# USB_SAO.net
KiCad netlist of a schematic drawn in EAGLE
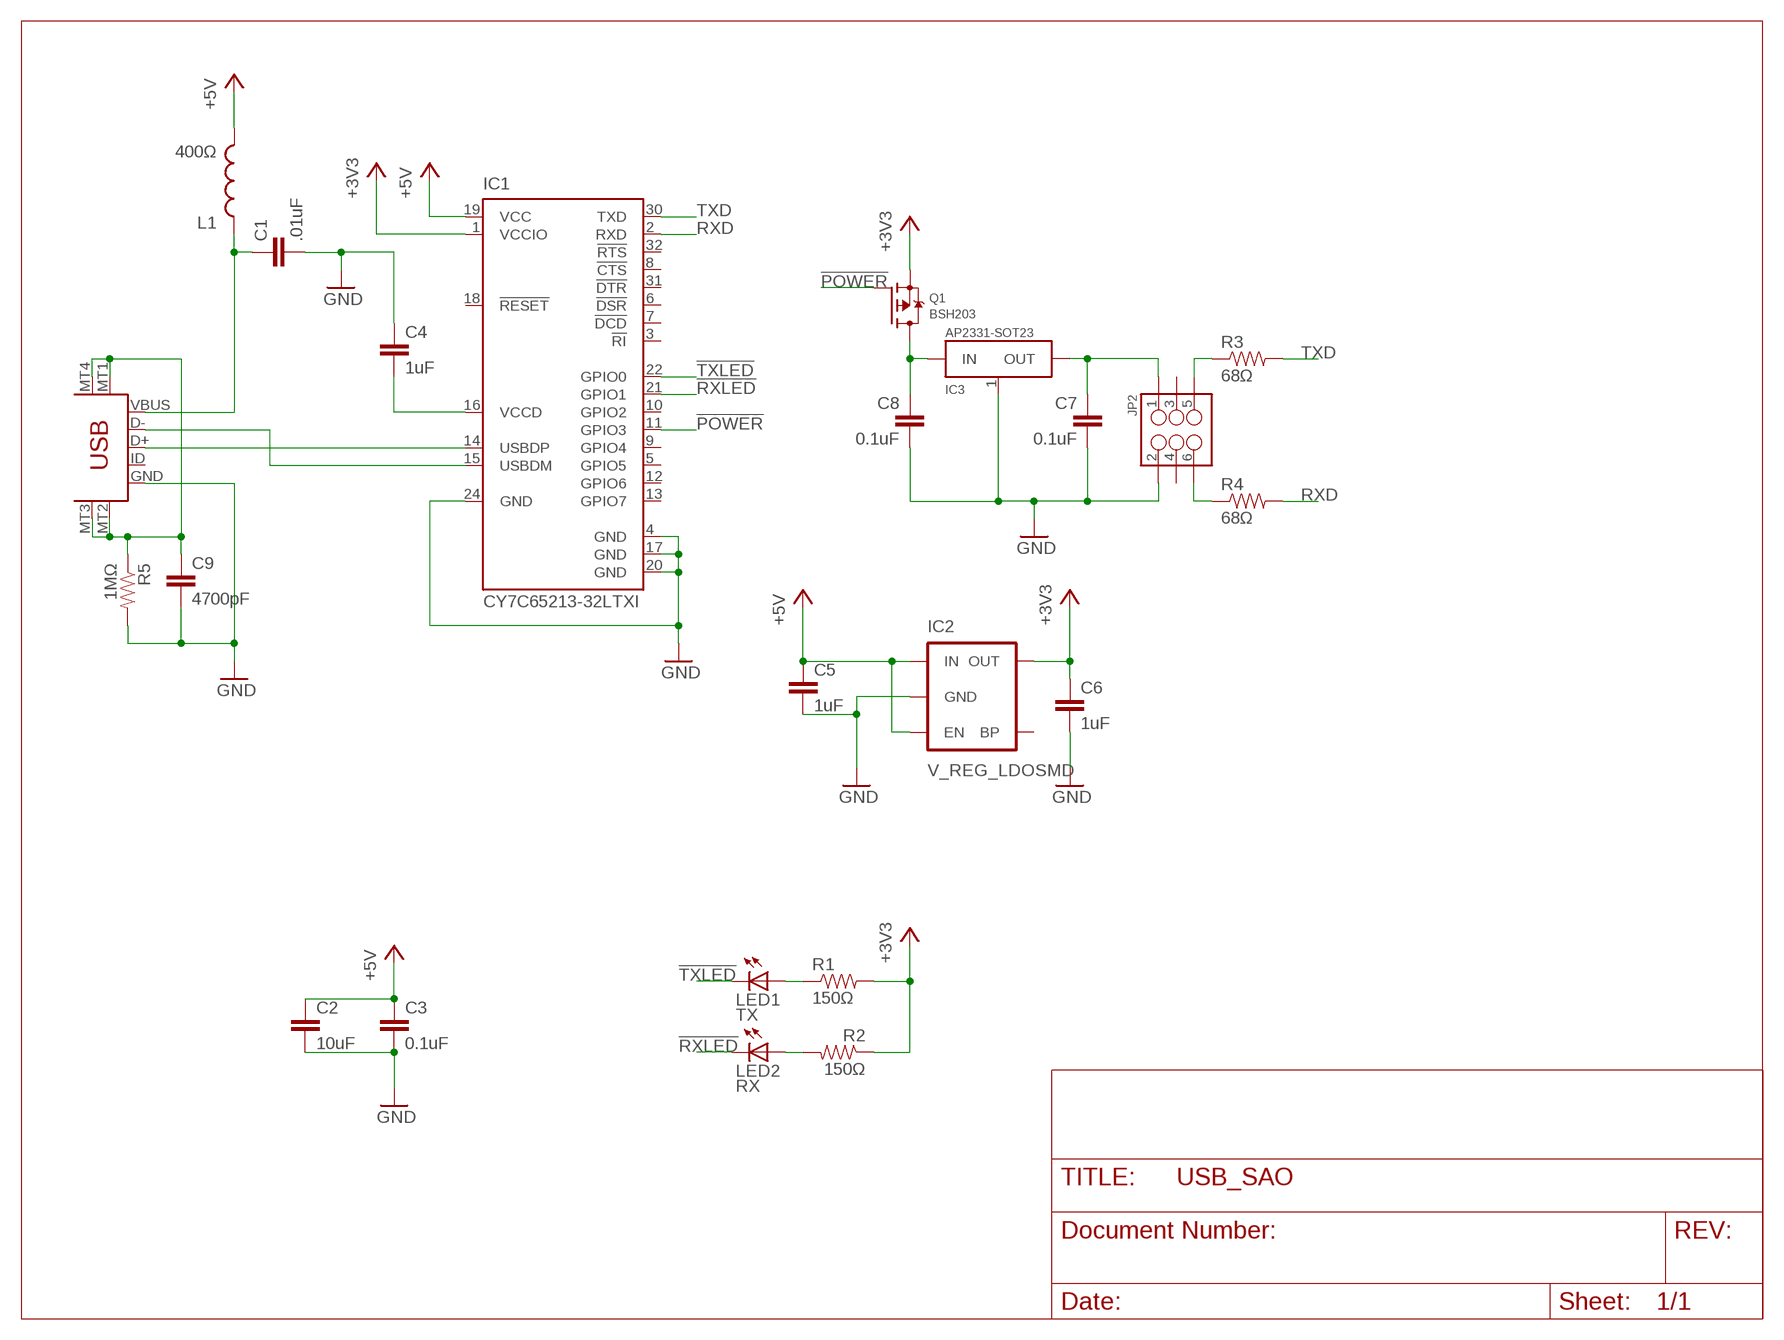
[diagram p0: schematic, sheet 1]

(export (version "E")
  (design (tool "Eeschema 10.0.6"))
  (components
    (comp (ref "C1")
      (value ".01uF")
      (footprint "eagle-import:0805")
      (libsource (lib "eagle-import") (part "CAP0805"))
    )
    (comp (ref "C2")
      (value "10uF")
      (footprint "eagle-import:0805")
      (libsource (lib "eagle-import") (part "CAP0805"))
    )
    (comp (ref "C3")
      (value "0.1uF")
      (footprint "eagle-import:0805")
      (libsource (lib "eagle-import") (part "CAP0805"))
    )
    (comp (ref "C4")
      (value "1uF")
      (footprint "eagle-import:0805")
      (libsource (lib "eagle-import") (part "CAP0805"))
    )
    (comp (ref "C5")
      (value "1uF")
      (footprint "eagle-import:0805")
      (libsource (lib "eagle-import") (part "CAP0805"))
    )
    (comp (ref "C6")
      (value "1uF")
      (footprint "eagle-import:0805")
      (libsource (lib "eagle-import") (part "CAP0805"))
    )
    (comp (ref "C7")
      (value "0.1uF")
      (footprint "eagle-import:0805")
      (libsource (lib "eagle-import") (part "CAP0805"))
    )
    (comp (ref "C8")
      (value "0.1uF")
      (footprint "eagle-import:0805")
      (libsource (lib "eagle-import") (part "CAP0805"))
    )
    (comp (ref "C9")
      (value "4700pF")
      (footprint "eagle-import:0805")
      (libsource (lib "eagle-import") (part "CAP0805"))
    )
    (comp (ref "IC1")
      (value "CY7C65213-32LTXI")
      (footprint "eagle-import:QFN32")
      (libsource (lib "eagle-import") (part "CY7C65213-32LTXI"))
    )
    (comp (ref "IC2")
      (value "V_REG_LDOSMD")
      (footprint "eagle-import:SOT23-5")
      (libsource (lib "eagle-import") (part "V_REG_LDOSMD"))
    )
    (comp (ref "IC3")
      (value "AP2331-SOT23")
      (footprint "eagle-import:SOT23-3")
      (libsource (lib "eagle-import") (part "AP2331-SOT23"))
    )
    (comp (ref "JP1")
      (value "USB-5PIN-MICROB")
      (footprint "eagle-import:USB-MICROB")
      (libsource (lib "eagle-import") (part "USB-5PIN-MICROB"))
    )
    (comp (ref "JP2")
      (value "M03X2NO_SILK")
      (footprint "eagle-import:2X3-NS")
      (libsource (lib "eagle-import") (part "M03X2NO_SILK"))
    )
    (comp (ref "L1")
      (value "400Ω")
      (footprint "eagle-import:0805")
      (libsource (lib "eagle-import") (part "INDUCTOR0805"))
    )
    (comp (ref "LED1")
      (value "TX")
      (footprint "eagle-import:CHIP-LED0805")
      (libsource (lib "eagle-import") (part "LEDCHIP-LED0805"))
    )
    (comp (ref "LED2")
      (value "RX")
      (footprint "eagle-import:CHIP-LED0805")
      (libsource (lib "eagle-import") (part "LEDCHIP-LED0805"))
    )
    (comp (ref "Q1")
      (value "BSH203")
      (footprint "eagle-import:SOT23-R")
      (libsource (lib "eagle-import") (part "MOSFET-P"))
    )
    (comp (ref "R1")
      (value "150Ω")
      (footprint "eagle-import:0805")
      (libsource (lib "eagle-import") (part "RESISTOR0805-RES"))
    )
    (comp (ref "R2")
      (value "150Ω")
      (footprint "eagle-import:0805")
      (libsource (lib "eagle-import") (part "RESISTOR0805-RES"))
    )
    (comp (ref "R3")
      (value "68Ω")
      (footprint "eagle-import:0805")
      (libsource (lib "eagle-import") (part "RESISTOR0805-RES"))
    )
    (comp (ref "R4")
      (value "68Ω")
      (footprint "eagle-import:0805")
      (libsource (lib "eagle-import") (part "RESISTOR0805-RES"))
    )
    (comp (ref "R5")
      (value "1MΩ")
      (footprint "eagle-import:0805")
      (libsource (lib "eagle-import") (part "RESISTOR0805-RES"))
    )
  )
  (nets
    (net (code "1") (name "+3V3") (class "Default")
      (node (ref "C6") (pin "1") (pinfunction "1_1") (pintype "passive"))
      (node (ref "IC1") (pin "1") (pinfunction "VCCIO_1") (pintype "power_in"))
      (node (ref "IC2") (pin "5") (pinfunction "OUT_5") (pintype "passive"))
      (node (ref "Q1") (pin "2") (pinfunction "S_2") (pintype "passive"))
      (node (ref "R1") (pin "2") (pinfunction "2_2") (pintype "passive"))
      (node (ref "R2") (pin "1") (pinfunction "1_1") (pintype "passive"))
    )
    (net (code "2") (name "+5V") (class "Default")
      (node (ref "C2") (pin "1") (pinfunction "1_1") (pintype "passive"))
      (node (ref "C3") (pin "1") (pinfunction "1_1") (pintype "passive"))
      (node (ref "C5") (pin "1") (pinfunction "1_1") (pintype "passive"))
      (node (ref "IC1") (pin "19") (pinfunction "VCC_19") (pintype "power_in"))
      (node (ref "IC2") (pin "1") (pinfunction "IN_1") (pintype "input"))
      (node (ref "IC2") (pin "3") (pinfunction "EN_3") (pintype "input"))
      (node (ref "L1") (pin "2") (pinfunction "2_2") (pintype "passive"))
    )
    (net (code "3") (name "/RXD") (class "Default")
      (node (ref "IC1") (pin "2") (pinfunction "RXD_2") (pintype "input"))
      (node (ref "R4") (pin "2") (pinfunction "2_2") (pintype "passive"))
    )
    (net (code "4") (name "/TXD") (class "Default")
      (node (ref "IC1") (pin "30") (pinfunction "TXD_30") (pintype "output"))
      (node (ref "R3") (pin "2") (pinfunction "2_2") (pintype "passive"))
    )
    (net (code "5") (name "/~{POWER}") (class "Default")
      (node (ref "IC1") (pin "11") (pinfunction "GPIO3_11") (pintype "bidirectional"))
      (node (ref "Q1") (pin "1") (pinfunction "G_1") (pintype "passive"))
    )
    (net (code "6") (name "/~{RXLED}") (class "Default")
      (node (ref "IC1") (pin "21") (pinfunction "GPIO1_21") (pintype "bidirectional"))
      (node (ref "LED2") (pin "C") (pinfunction "C_C") (pintype "passive"))
    )
    (net (code "7") (name "/~{TXLED}") (class "Default")
      (node (ref "IC1") (pin "22") (pinfunction "GPIO0_22") (pintype "bidirectional"))
      (node (ref "LED1") (pin "C") (pinfunction "C_C") (pintype "passive"))
    )
    (net (code "8") (name "GND") (class "Default")
      (node (ref "C1") (pin "2") (pinfunction "2_2") (pintype "passive"))
      (node (ref "C2") (pin "2") (pinfunction "2_2") (pintype "passive"))
      (node (ref "C3") (pin "2") (pinfunction "2_2") (pintype "passive"))
      (node (ref "C4") (pin "1") (pinfunction "1_1") (pintype "passive"))
      (node (ref "C5") (pin "2") (pinfunction "2_2") (pintype "passive"))
      (node (ref "C6") (pin "2") (pinfunction "2_2") (pintype "passive"))
      (node (ref "C7") (pin "2") (pinfunction "2_2") (pintype "passive"))
      (node (ref "C8") (pin "2") (pinfunction "2_2") (pintype "passive"))
      (node (ref "C9") (pin "2") (pinfunction "2_2") (pintype "passive"))
      (node (ref "IC1") (pin "17") (pinfunction "GND_17") (pintype "power_in"))
      (node (ref "IC1") (pin "20") (pinfunction "GND_20") (pintype "power_in"))
      (node (ref "IC1") (pin "24") (pinfunction "GND_24") (pintype "power_in"))
      (node (ref "IC1") (pin "4") (pinfunction "GND_4") (pintype "power_in"))
      (node (ref "IC2") (pin "2") (pinfunction "GND_2") (pintype "input"))
      (node (ref "IC3") (pin "1") (pinfunction "GND_1") (pintype "power_in"))
      (node (ref "JP1") (pin "GND") (pinfunction "GND_GND") (pintype "bidirectional"))
      (node (ref "JP2") (pin "2") (pinfunction "2_2") (pintype "bidirectional"))
      (node (ref "R5") (pin "2") (pinfunction "2_2") (pintype "passive"))
    )
    (net (code "9") (name "Net-(C1-Pad1)") (class "Default")
      (node (ref "C1") (pin "1") (pinfunction "1_1") (pintype "passive"))
      (node (ref "JP1") (pin "VBUS") (pinfunction "VBUS_VBUS") (pintype "bidirectional"))
      (node (ref "L1") (pin "1") (pinfunction "1_1") (pintype "passive"))
    )
    (net (code "10") (name "Net-(IC1-USBDM)") (class "Default")
      (node (ref "IC1") (pin "15") (pinfunction "USBDM_15") (pintype "bidirectional"))
      (node (ref "JP1") (pin "D-") (pinfunction "D-_D-") (pintype "bidirectional"))
    )
    (net (code "11") (name "Net-(IC1-USBDP)") (class "Default")
      (node (ref "IC1") (pin "14") (pinfunction "USBDP_14") (pintype "bidirectional"))
      (node (ref "JP1") (pin "D+") (pinfunction "D+_D+") (pintype "bidirectional"))
    )
    (net (code "12") (name "Net-(IC1-VCCD)") (class "Default")
      (node (ref "C4") (pin "2") (pinfunction "2_2") (pintype "passive"))
      (node (ref "IC1") (pin "16") (pinfunction "VCCD_16") (pintype "output"))
    )
    (net (code "13") (name "Net-(IC3-IN)") (class "Default")
      (node (ref "C8") (pin "1") (pinfunction "1_1") (pintype "passive"))
      (node (ref "IC3") (pin "3") (pinfunction "IN_3") (pintype "power_in"))
      (node (ref "Q1") (pin "3") (pinfunction "D_3") (pintype "passive"))
    )
    (net (code "14") (name "Net-(IC3-OUT)") (class "Default")
      (node (ref "C7") (pin "1") (pinfunction "1_1") (pintype "passive"))
      (node (ref "IC3") (pin "2") (pinfunction "OUT_2") (pintype "output"))
      (node (ref "JP2") (pin "1") (pinfunction "1_1") (pintype "bidirectional"))
    )
    (net (code "15") (name "Net-(JP1-MTN1)") (class "Default")
      (node (ref "C9") (pin "1") (pinfunction "1_1") (pintype "passive"))
      (node (ref "JP1") (pin "MT1") (pinfunction "MTN1_MT1") (pintype "bidirectional"))
      (node (ref "JP1") (pin "MT2") (pinfunction "MTN3_MT2") (pintype "bidirectional"))
      (node (ref "JP1") (pin "MT3") (pinfunction "MTN4_MT3") (pintype "bidirectional"))
      (node (ref "JP1") (pin "MT4") (pinfunction "MTN2_MT4") (pintype "bidirectional"))
      (node (ref "R5") (pin "1") (pinfunction "1_1") (pintype "passive"))
    )
    (net (code "16") (name "Net-(JP2-Pad5)") (class "Default")
      (node (ref "JP2") (pin "5") (pinfunction "5_5") (pintype "bidirectional"))
      (node (ref "R3") (pin "1") (pinfunction "1_1") (pintype "passive"))
    )
    (net (code "17") (name "Net-(JP2-Pad6)") (class "Default")
      (node (ref "JP2") (pin "6") (pinfunction "6_6") (pintype "bidirectional"))
      (node (ref "R4") (pin "1") (pinfunction "1_1") (pintype "passive"))
    )
    (net (code "18") (name "Net-(LED1-PadA)") (class "Default")
      (node (ref "LED1") (pin "A") (pinfunction "A_A") (pintype "passive"))
      (node (ref "R1") (pin "1") (pinfunction "1_1") (pintype "passive"))
    )
    (net (code "19") (name "Net-(LED2-PadA)") (class "Default")
      (node (ref "LED2") (pin "A") (pinfunction "A_A") (pintype "passive"))
      (node (ref "R2") (pin "2") (pinfunction "2_2") (pintype "passive"))
    )
    (net (code "20") (name "unconnected-(IC1-GPIO2-Pad10)") (class "Default")
      (node (ref "IC1") (pin "10") (pinfunction "GPIO2_10") (pintype "bidirectional"))
    )
    (net (code "21") (name "unconnected-(IC1-GPIO4-Pad9)") (class "Default")
      (node (ref "IC1") (pin "9") (pinfunction "GPIO4_9") (pintype "bidirectional"))
    )
    (net (code "22") (name "unconnected-(IC1-GPIO5-Pad5)") (class "Default")
      (node (ref "IC1") (pin "5") (pinfunction "GPIO5_5") (pintype "bidirectional"))
    )
    (net (code "23") (name "unconnected-(IC1-GPIO6-Pad12)") (class "Default")
      (node (ref "IC1") (pin "12") (pinfunction "GPIO6_12") (pintype "bidirectional"))
    )
    (net (code "24") (name "unconnected-(IC1-GPIO7-Pad13)") (class "Default")
      (node (ref "IC1") (pin "13") (pinfunction "GPIO7_13") (pintype "bidirectional"))
    )
    (net (code "25") (name "unconnected-(IC1-~{CTS}-Pad8)") (class "Default")
      (node (ref "IC1") (pin "8") (pinfunction "~{CTS}_8") (pintype "input"))
    )
    (net (code "26") (name "unconnected-(IC1-~{DCD}-Pad7)") (class "Default")
      (node (ref "IC1") (pin "7") (pinfunction "~{DCD}_7") (pintype "input"))
    )
    (net (code "27") (name "unconnected-(IC1-~{DSR}-Pad6)") (class "Default")
      (node (ref "IC1") (pin "6") (pinfunction "~{DSR}_6") (pintype "input"))
    )
    (net (code "28") (name "unconnected-(IC1-~{DTR}-Pad31)") (class "Default")
      (node (ref "IC1") (pin "31") (pinfunction "~{DTR}_31") (pintype "output"))
    )
    (net (code "29") (name "unconnected-(IC1-~{RESET}-Pad18)") (class "Default")
      (node (ref "IC1") (pin "18") (pinfunction "~{RESET}_18") (pintype "input"))
    )
    (net (code "30") (name "unconnected-(IC1-~{RI}-Pad3)") (class "Default")
      (node (ref "IC1") (pin "3") (pinfunction "~{RI}_3") (pintype "input"))
    )
    (net (code "31") (name "unconnected-(IC1-~{RTS}-Pad32)") (class "Default")
      (node (ref "IC1") (pin "32") (pinfunction "~{RTS}_32") (pintype "output"))
    )
    (net (code "32") (name "unconnected-(IC2-BP-Pad4)") (class "Default")
      (node (ref "IC2") (pin "4") (pinfunction "BP_4") (pintype "input"))
    )
    (net (code "33") (name "unconnected-(JP1-PadID)") (class "Default")
      (node (ref "JP1") (pin "ID") (pinfunction "ID_ID") (pintype "bidirectional"))
    )
    (net (code "34") (name "unconnected-(JP2-Pad3)") (class "Default")
      (node (ref "JP2") (pin "3") (pinfunction "3_3") (pintype "bidirectional"))
    )
    (net (code "35") (name "unconnected-(JP2-Pad4)") (class "Default")
      (node (ref "JP2") (pin "4") (pinfunction "4_4") (pintype "bidirectional"))
    )
  )
)
